# Pi3_Power_hat_Rev1.net
KiCad netlist of a schematic drawn in EAGLE
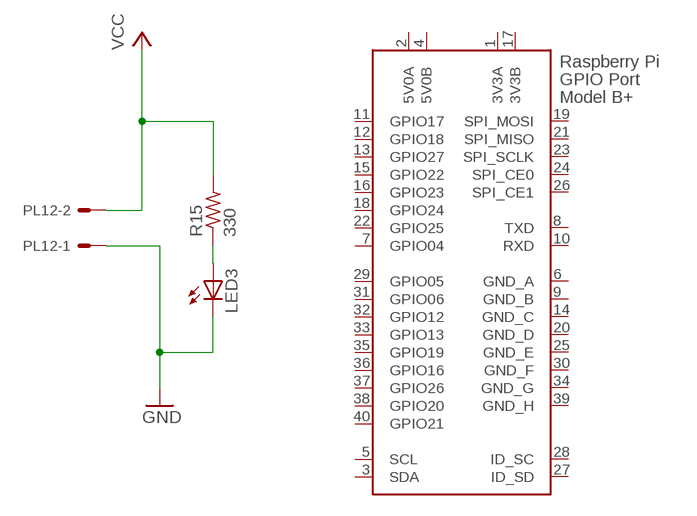
[diagram p0: schematic, sheet 1]
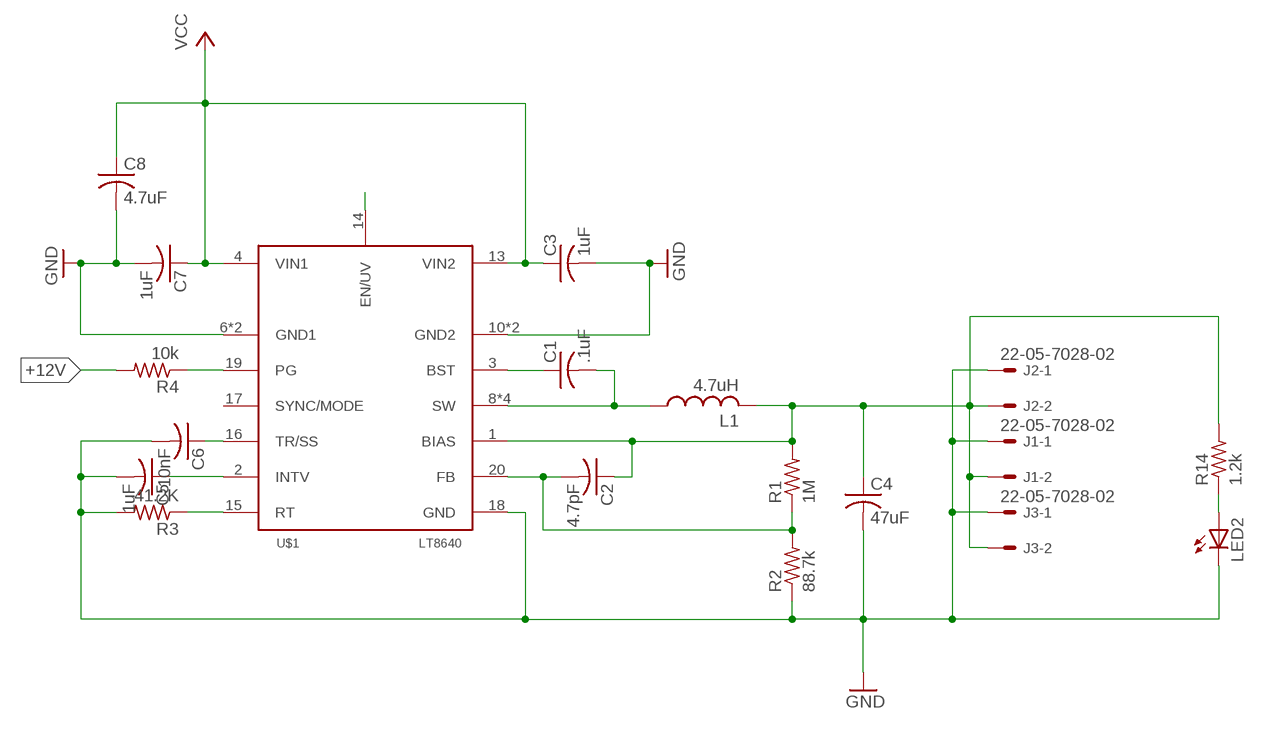
[diagram p1: schematic, sheet 2]
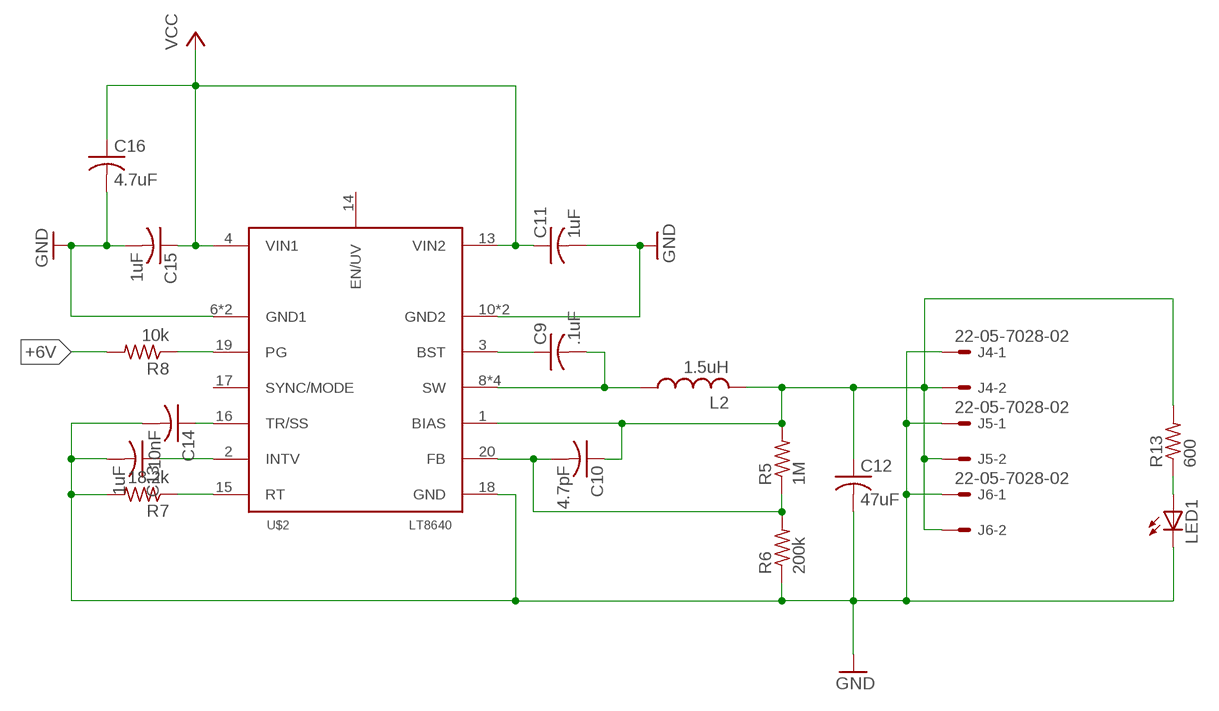
[diagram p2: schematic, sheet 3]
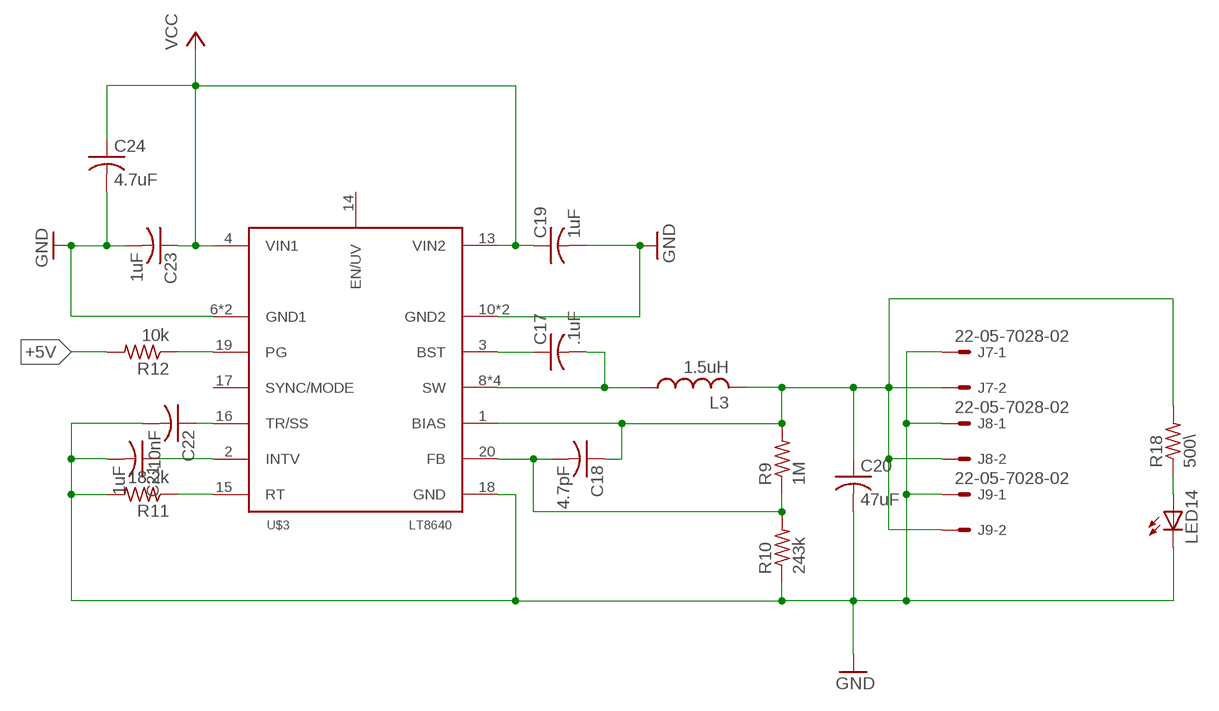
[diagram p3: schematic, sheet 4]

(export (version "E")
  (design (tool "Eeschema 10.0.6"))
  (components
    (comp (ref "LED3")
      (value "LEDCHIP-LED0603")
      (footprint "eagle-import:CHIP-LED0603")
      (libsource (lib "eagle-import") (part "LEDCHIP-LED0603"))
    )
    (comp (ref "PL12")
      (value "555X-2H")
      (footprint "eagle-import:5569-2")
      (libsource (lib "eagle-import") (part "555X-2H"))
    )
    (comp (ref "R15")
      (value "330")
      (footprint "eagle-import:R0402")
      (libsource (lib "eagle-import") (part "R-US_R0402"))
    )
    (comp (ref "X1")
      (value "RASPI_BOARD_B+#_E4P")
      (footprint "eagle-import:RASPI_BOARD_B+_EDGES_4DRILL_PAD")
      (libsource (lib "eagle-import") (part "RASPI_BOARD_B+#_E4P"))
    )
    (comp (ref "C1")
      (value ".1uF")
      (footprint "eagle-import:C0402")
      (libsource (lib "eagle-import") (part "C-USC0402"))
    )
    (comp (ref "C2")
      (value "4.7pF")
      (footprint "eagle-import:C0402")
      (libsource (lib "eagle-import") (part "C-USC0402"))
    )
    (comp (ref "C3")
      (value "1uF")
      (footprint "eagle-import:C0402")
      (libsource (lib "eagle-import") (part "C-USC0402"))
    )
    (comp (ref "C4")
      (value "47uF")
      (footprint "eagle-import:C1210")
      (libsource (lib "eagle-import") (part "C-USC1210"))
    )
    (comp (ref "C5")
      (value "1uF")
      (footprint "eagle-import:C0402")
      (libsource (lib "eagle-import") (part "C-USC0402"))
    )
    (comp (ref "C6")
      (value "10nF")
      (footprint "eagle-import:C0402")
      (libsource (lib "eagle-import") (part "C-USC0402"))
    )
    (comp (ref "C7")
      (value "1uF")
      (footprint "eagle-import:C0402")
      (libsource (lib "eagle-import") (part "C-USC0402"))
    )
    (comp (ref "C8")
      (value "4.7uF")
      (footprint "eagle-import:C0603")
      (libsource (lib "eagle-import") (part "C-USC0603"))
    )
    (comp (ref "J1")
      (value "22-05-7028-02")
      (footprint "eagle-import:7395-02")
      (libsource (lib "eagle-import") (part "22-?-0205-7028"))
    )
    (comp (ref "J2")
      (value "22-05-7028-02")
      (footprint "eagle-import:7395-02")
      (libsource (lib "eagle-import") (part "22-?-0205-7028"))
    )
    (comp (ref "J3")
      (value "22-05-7028-02")
      (footprint "eagle-import:7395-02")
      (libsource (lib "eagle-import") (part "22-?-0205-7028"))
    )
    (comp (ref "L1")
      (value "4.7uH")
      (footprint "eagle-import:IHLP2525EZER4R7M01-FOOT")
      (libsource (lib "eagle-import") (part "L-USIHLP2525EZER4R7M01"))
    )
    (comp (ref "LED2")
      (value "LEDCHIP-LED0603")
      (footprint "eagle-import:CHIP-LED0603")
      (libsource (lib "eagle-import") (part "LEDCHIP-LED0603"))
    )
    (comp (ref "R1")
      (value "1M")
      (footprint "eagle-import:R0402")
      (libsource (lib "eagle-import") (part "R-US_R0402"))
    )
    (comp (ref "R2")
      (value "88.7k")
      (footprint "eagle-import:R0402")
      (libsource (lib "eagle-import") (part "R-US_R0402"))
    )
    (comp (ref "R3")
      (value "41.2K")
      (footprint "eagle-import:R0402")
      (libsource (lib "eagle-import") (part "R-US_R0402"))
    )
    (comp (ref "R4")
      (value "10k")
      (footprint "eagle-import:R0402")
      (libsource (lib "eagle-import") (part "R-US_R0402"))
    )
    (comp (ref "R14")
      (value "1.2k")
      (footprint "eagle-import:R0402")
      (libsource (lib "eagle-import") (part "R-US_R0402"))
    )
    (comp (ref "U$1")
      (value "LT8640")
      (footprint "eagle-import:LT8640_FOOT")
      (libsource (lib "eagle-import") (part "LT8640"))
    )
    (comp (ref "C9")
      (value ".1uF")
      (footprint "eagle-import:C0402")
      (libsource (lib "eagle-import") (part "C-USC0402"))
    )
    (comp (ref "C10")
      (value "4.7pF")
      (footprint "eagle-import:C0402")
      (libsource (lib "eagle-import") (part "C-USC0402"))
    )
    (comp (ref "C11")
      (value "1uF")
      (footprint "eagle-import:C0402")
      (libsource (lib "eagle-import") (part "C-USC0402"))
    )
    (comp (ref "C12")
      (value "47uF")
      (footprint "eagle-import:C1210")
      (libsource (lib "eagle-import") (part "C-USC1210"))
    )
    (comp (ref "C13")
      (value "1uF")
      (footprint "eagle-import:C0402")
      (libsource (lib "eagle-import") (part "C-USC0402"))
    )
    (comp (ref "C14")
      (value "10nF")
      (footprint "eagle-import:C0402")
      (libsource (lib "eagle-import") (part "C-USC0402"))
    )
    (comp (ref "C15")
      (value "1uF")
      (footprint "eagle-import:C0402")
      (libsource (lib "eagle-import") (part "C-USC0402"))
    )
    (comp (ref "C16")
      (value "4.7uF")
      (footprint "eagle-import:C0603")
      (libsource (lib "eagle-import") (part "C-USC0603"))
    )
    (comp (ref "J4")
      (value "22-05-7028-02")
      (footprint "eagle-import:7395-02")
      (libsource (lib "eagle-import") (part "22-?-0205-7028"))
    )
    (comp (ref "J5")
      (value "22-05-7028-02")
      (footprint "eagle-import:7395-02")
      (libsource (lib "eagle-import") (part "22-?-0205-7028"))
    )
    (comp (ref "J6")
      (value "22-05-7028-02")
      (footprint "eagle-import:7395-02")
      (libsource (lib "eagle-import") (part "22-?-0205-7028"))
    )
    (comp (ref "L2")
      (value "1.5uH")
      (footprint "eagle-import:IHLP2525EZER4R7M01-FOOT")
      (libsource (lib "eagle-import") (part "L-USIHLP2525EZER4R7M01"))
    )
    (comp (ref "LED1")
      (value "LEDCHIP-LED0603")
      (footprint "eagle-import:CHIP-LED0603")
      (libsource (lib "eagle-import") (part "LEDCHIP-LED0603"))
    )
    (comp (ref "R5")
      (value "1M")
      (footprint "eagle-import:R0402")
      (libsource (lib "eagle-import") (part "R-US_R0402"))
    )
    (comp (ref "R6")
      (value "200k")
      (footprint "eagle-import:R0402")
      (libsource (lib "eagle-import") (part "R-US_R0402"))
    )
    (comp (ref "R7")
      (value "18.2k")
      (footprint "eagle-import:R0402")
      (libsource (lib "eagle-import") (part "R-US_R0402"))
    )
    (comp (ref "R8")
      (value "10k")
      (footprint "eagle-import:R0402")
      (libsource (lib "eagle-import") (part "R-US_R0402"))
    )
    (comp (ref "R13")
      (value "600")
      (footprint "eagle-import:R0402")
      (libsource (lib "eagle-import") (part "R-US_R0402"))
    )
    (comp (ref "U$2")
      (value "LT8640")
      (footprint "eagle-import:LT8640_FOOT")
      (libsource (lib "eagle-import") (part "LT8640"))
    )
    (comp (ref "C17")
      (value ".1uF")
      (footprint "eagle-import:C0402")
      (libsource (lib "eagle-import") (part "C-USC0402"))
    )
    (comp (ref "C18")
      (value "4.7pF")
      (footprint "eagle-import:C0402")
      (libsource (lib "eagle-import") (part "C-USC0402"))
    )
    (comp (ref "C19")
      (value "1uF")
      (footprint "eagle-import:C0402")
      (libsource (lib "eagle-import") (part "C-USC0402"))
    )
    (comp (ref "C20")
      (value "47uF")
      (footprint "eagle-import:C1210")
      (libsource (lib "eagle-import") (part "C-USC1210"))
    )
    (comp (ref "C21")
      (value "1uF")
      (footprint "eagle-import:C0402")
      (libsource (lib "eagle-import") (part "C-USC0402"))
    )
    (comp (ref "C22")
      (value "10nF")
      (footprint "eagle-import:C0402")
      (libsource (lib "eagle-import") (part "C-USC0402"))
    )
    (comp (ref "C23")
      (value "1uF")
      (footprint "eagle-import:C0402")
      (libsource (lib "eagle-import") (part "C-USC0402"))
    )
    (comp (ref "C24")
      (value "4.7uF")
      (footprint "eagle-import:C0603")
      (libsource (lib "eagle-import") (part "C-USC0603"))
    )
    (comp (ref "J7")
      (value "22-05-7028-02")
      (footprint "eagle-import:7395-02")
      (libsource (lib "eagle-import") (part "22-?-0205-7028"))
    )
    (comp (ref "J8")
      (value "22-05-7028-02")
      (footprint "eagle-import:7395-02")
      (libsource (lib "eagle-import") (part "22-?-0205-7028"))
    )
    (comp (ref "J9")
      (value "22-05-7028-02")
      (footprint "eagle-import:7395-02")
      (libsource (lib "eagle-import") (part "22-?-0205-7028"))
    )
    (comp (ref "L3")
      (value "1.5uH")
      (footprint "eagle-import:IHLP2525EZER4R7M01-FOOT")
      (libsource (lib "eagle-import") (part "L-USIHLP2525EZER4R7M01"))
    )
    (comp (ref "LED14")
      (value "LEDCHIP-LED0603")
      (footprint "eagle-import:CHIP-LED0603")
      (libsource (lib "eagle-import") (part "LEDCHIP-LED0603"))
    )
    (comp (ref "R9")
      (value "1M")
      (footprint "eagle-import:R0402")
      (libsource (lib "eagle-import") (part "R-US_R0402"))
    )
    (comp (ref "R10")
      (value "243k")
      (footprint "eagle-import:R0402")
      (libsource (lib "eagle-import") (part "R-US_R0402"))
    )
    (comp (ref "R11")
      (value "18.2k")
      (footprint "eagle-import:R0402")
      (libsource (lib "eagle-import") (part "R-US_R0402"))
    )
    (comp (ref "R12")
      (value "10k")
      (footprint "eagle-import:R0402")
      (libsource (lib "eagle-import") (part "R-US_R0402"))
    )
    (comp (ref "R18")
      (value "500\\")
      (footprint "eagle-import:R0402")
      (libsource (lib "eagle-import") (part "R-US_R0402"))
    )
    (comp (ref "U$3")
      (value "LT8640")
      (footprint "eagle-import:LT8640_FOOT")
      (libsource (lib "eagle-import") (part "LT8640"))
    )
  )
  (nets
    (net (code "1") (name "+5V") (class "Default")
      (node (ref "C18") (pin "1") (pinfunction "1_1") (pintype "passive"))
      (node (ref "C20") (pin "1") (pinfunction "1_1") (pintype "passive"))
      (node (ref "J7") (pin "2") (pinfunction "S_2") (pintype "passive"))
      (node (ref "J8") (pin "2") (pinfunction "S_2") (pintype "passive"))
      (node (ref "J9") (pin "2") (pinfunction "S_2") (pintype "passive"))
      (node (ref "L3") (pin "2") (pinfunction "2_2") (pintype "passive"))
      (node (ref "R12") (pin "2") (pinfunction "2_2") (pintype "passive"))
      (node (ref "R18") (pin "2") (pinfunction "2_2") (pintype "passive"))
      (node (ref "R9") (pin "2") (pinfunction "2_2") (pintype "passive"))
      (node (ref "U$3") (pin "1") (pinfunction "BIAS_1") (pintype "bidirectional"))
    )
    (net (code "2") (name "+6V") (class "Default")
      (node (ref "C10") (pin "1") (pinfunction "1_1") (pintype "passive"))
      (node (ref "C12") (pin "1") (pinfunction "1_1") (pintype "passive"))
      (node (ref "J4") (pin "2") (pinfunction "S_2") (pintype "passive"))
      (node (ref "J5") (pin "2") (pinfunction "S_2") (pintype "passive"))
      (node (ref "J6") (pin "2") (pinfunction "S_2") (pintype "passive"))
      (node (ref "L2") (pin "2") (pinfunction "2_2") (pintype "passive"))
      (node (ref "R13") (pin "2") (pinfunction "2_2") (pintype "passive"))
      (node (ref "R5") (pin "2") (pinfunction "2_2") (pintype "passive"))
      (node (ref "R8") (pin "2") (pinfunction "2_2") (pintype "passive"))
      (node (ref "U$2") (pin "1") (pinfunction "BIAS_1") (pintype "bidirectional"))
    )
    (net (code "3") (name "+12V") (class "Default")
      (node (ref "C2") (pin "1") (pinfunction "1_1") (pintype "passive"))
      (node (ref "C4") (pin "1") (pinfunction "1_1") (pintype "passive"))
      (node (ref "J1") (pin "2") (pinfunction "S_2") (pintype "passive"))
      (node (ref "J2") (pin "2") (pinfunction "S_2") (pintype "passive"))
      (node (ref "J3") (pin "2") (pinfunction "S_2") (pintype "passive"))
      (node (ref "L1") (pin "2") (pinfunction "2_2") (pintype "passive"))
      (node (ref "R1") (pin "2") (pinfunction "2_2") (pintype "passive"))
      (node (ref "R14") (pin "2") (pinfunction "2_2") (pintype "passive"))
      (node (ref "R4") (pin "2") (pinfunction "2_2") (pintype "passive"))
      (node (ref "U$1") (pin "1") (pinfunction "BIAS_1") (pintype "bidirectional"))
    )
    (net (code "4") (name "3V3A") (class "Default")
      (node (ref "X1") (pin "1") (pinfunction "3V3A_1") (pintype "power_in"))
    )
    (net (code "5") (name "3V3B") (class "Default")
      (node (ref "X1") (pin "17") (pinfunction "3V3B_17") (pintype "power_in"))
    )
    (net (code "6") (name "5V0A") (class "Default")
      (node (ref "X1") (pin "2") (pinfunction "5V0A_2") (pintype "power_in"))
    )
    (net (code "7") (name "5V0B") (class "Default")
      (node (ref "X1") (pin "4") (pinfunction "5V0B_4") (pintype "power_in"))
    )
    (net (code "8") (name "GND") (class "Default")
      (node (ref "C11") (pin "2") (pinfunction "2_2") (pintype "passive"))
      (node (ref "C12") (pin "2") (pinfunction "2_2") (pintype "passive"))
      (node (ref "C13") (pin "2") (pinfunction "2_2") (pintype "passive"))
      (node (ref "C14") (pin "2") (pinfunction "2_2") (pintype "passive"))
      (node (ref "C15") (pin "2") (pinfunction "2_2") (pintype "passive"))
      (node (ref "C16") (pin "2") (pinfunction "2_2") (pintype "passive"))
      (node (ref "C19") (pin "2") (pinfunction "2_2") (pintype "passive"))
      (node (ref "C20") (pin "2") (pinfunction "2_2") (pintype "passive"))
      (node (ref "C21") (pin "2") (pinfunction "2_2") (pintype "passive"))
      (node (ref "C22") (pin "2") (pinfunction "2_2") (pintype "passive"))
      (node (ref "C23") (pin "2") (pinfunction "2_2") (pintype "passive"))
      (node (ref "C24") (pin "2") (pinfunction "2_2") (pintype "passive"))
      (node (ref "C3") (pin "2") (pinfunction "2_2") (pintype "passive"))
      (node (ref "C4") (pin "2") (pinfunction "2_2") (pintype "passive"))
      (node (ref "C5") (pin "2") (pinfunction "2_2") (pintype "passive"))
      (node (ref "C6") (pin "2") (pinfunction "2_2") (pintype "passive"))
      (node (ref "C7") (pin "2") (pinfunction "2_2") (pintype "passive"))
      (node (ref "C8") (pin "2") (pinfunction "2_2") (pintype "passive"))
      (node (ref "J1") (pin "1") (pinfunction "S_1") (pintype "passive"))
      (node (ref "J2") (pin "1") (pinfunction "S_1") (pintype "passive"))
      (node (ref "J3") (pin "1") (pinfunction "S_1") (pintype "passive"))
      (node (ref "J4") (pin "1") (pinfunction "S_1") (pintype "passive"))
      (node (ref "J5") (pin "1") (pinfunction "S_1") (pintype "passive"))
      (node (ref "J6") (pin "1") (pinfunction "S_1") (pintype "passive"))
      (node (ref "J7") (pin "1") (pinfunction "S_1") (pintype "passive"))
      (node (ref "J8") (pin "1") (pinfunction "S_1") (pintype "passive"))
      (node (ref "J9") (pin "1") (pinfunction "S_1") (pintype "passive"))
      (node (ref "LED1") (pin "C") (pinfunction "C_C") (pintype "passive"))
      (node (ref "LED14") (pin "C") (pinfunction "C_C") (pintype "passive"))
      (node (ref "LED2") (pin "C") (pinfunction "C_C") (pintype "passive"))
      (node (ref "LED3") (pin "C") (pinfunction "C_C") (pintype "passive"))
      (node (ref "PL12") (pin "1") (pinfunction "S_1") (pintype "passive"))
      (node (ref "R10") (pin "1") (pinfunction "1_1") (pintype "passive"))
      (node (ref "R11") (pin "2") (pinfunction "2_2") (pintype "passive"))
      (node (ref "R2") (pin "1") (pinfunction "1_1") (pintype "passive"))
      (node (ref "R3") (pin "2") (pinfunction "2_2") (pintype "passive"))
      (node (ref "R6") (pin "1") (pinfunction "1_1") (pintype "passive"))
      (node (ref "R7") (pin "2") (pinfunction "2_2") (pintype "passive"))
      (node (ref "U$1") (pin "10") (pinfunction "GND2_10") (pintype "bidirectional"))
      (node (ref "U$1") (pin "11") (pinfunction "GND2_11") (pintype "bidirectional"))
      (node (ref "U$1") (pin "18") (pinfunction "GND_18") (pintype "bidirectional"))
      (node (ref "U$1") (pin "6") (pinfunction "GND1_6") (pintype "bidirectional"))
      (node (ref "U$1") (pin "7") (pinfunction "GND1_7") (pintype "bidirectional"))
      (node (ref "U$2") (pin "10") (pinfunction "GND2_10") (pintype "bidirectional"))
      (node (ref "U$2") (pin "11") (pinfunction "GND2_11") (pintype "bidirectional"))
      (node (ref "U$2") (pin "18") (pinfunction "GND_18") (pintype "bidirectional"))
      (node (ref "U$2") (pin "6") (pinfunction "GND1_6") (pintype "bidirectional"))
      (node (ref "U$2") (pin "7") (pinfunction "GND1_7") (pintype "bidirectional"))
      (node (ref "U$3") (pin "10") (pinfunction "GND2_10") (pintype "bidirectional"))
      (node (ref "U$3") (pin "11") (pinfunction "GND2_11") (pintype "bidirectional"))
      (node (ref "U$3") (pin "18") (pinfunction "GND_18") (pintype "bidirectional"))
      (node (ref "U$3") (pin "6") (pinfunction "GND1_6") (pintype "bidirectional"))
      (node (ref "U$3") (pin "7") (pinfunction "GND1_7") (pintype "bidirectional"))
    )
    (net (code "9") (name "GND_A") (class "Default")
      (node (ref "X1") (pin "6") (pinfunction "GND_A_6") (pintype "power_in"))
    )
    (net (code "10") (name "GND_B") (class "Default")
      (node (ref "X1") (pin "9") (pinfunction "GND_B_9") (pintype "power_in"))
    )
    (net (code "11") (name "GND_C") (class "Default")
      (node (ref "X1") (pin "14") (pinfunction "GND_C_14") (pintype "power_in"))
    )
    (net (code "12") (name "GND_D") (class "Default")
      (node (ref "X1") (pin "20") (pinfunction "GND_D_20") (pintype "power_in"))
    )
    (net (code "13") (name "GND_E") (class "Default")
      (node (ref "X1") (pin "25") (pinfunction "GND_E_25") (pintype "power_in"))
    )
    (net (code "14") (name "GND_F") (class "Default")
      (node (ref "X1") (pin "30") (pinfunction "GND_F_30") (pintype "power_in"))
    )
    (net (code "15") (name "GND_G") (class "Default")
      (node (ref "X1") (pin "34") (pinfunction "GND_G_34") (pintype "power_in"))
    )
    (net (code "16") (name "GND_H") (class "Default")
      (node (ref "X1") (pin "39") (pinfunction "GND_H_39") (pintype "power_in"))
    )
    (net (code "17") (name "Net-(C1-Pad2)") (class "Default")
      (node (ref "C1") (pin "2") (pinfunction "2_2") (pintype "passive"))
      (node (ref "L1") (pin "1") (pinfunction "1_1") (pintype "passive"))
      (node (ref "U$1") (pin "21") (pinfunction "SW_21") (pintype "bidirectional"))
      (node (ref "U$1") (pin "22") (pinfunction "SW_22") (pintype "bidirectional"))
      (node (ref "U$1") (pin "8") (pinfunction "SW_8") (pintype "bidirectional"))
      (node (ref "U$1") (pin "9") (pinfunction "SW_9") (pintype "bidirectional"))
    )
    (net (code "18") (name "Net-(C9-Pad2)") (class "Default")
      (node (ref "C9") (pin "2") (pinfunction "2_2") (pintype "passive"))
      (node (ref "L2") (pin "1") (pinfunction "1_1") (pintype "passive"))
      (node (ref "U$2") (pin "21") (pinfunction "SW_21") (pintype "bidirectional"))
      (node (ref "U$2") (pin "22") (pinfunction "SW_22") (pintype "bidirectional"))
      (node (ref "U$2") (pin "8") (pinfunction "SW_8") (pintype "bidirectional"))
      (node (ref "U$2") (pin "9") (pinfunction "SW_9") (pintype "bidirectional"))
    )
    (net (code "19") (name "Net-(C17-Pad2)") (class "Default")
      (node (ref "C17") (pin "2") (pinfunction "2_2") (pintype "passive"))
      (node (ref "L3") (pin "1") (pinfunction "1_1") (pintype "passive"))
      (node (ref "U$3") (pin "21") (pinfunction "SW_21") (pintype "bidirectional"))
      (node (ref "U$3") (pin "22") (pinfunction "SW_22") (pintype "bidirectional"))
      (node (ref "U$3") (pin "8") (pinfunction "SW_8") (pintype "bidirectional"))
      (node (ref "U$3") (pin "9") (pinfunction "SW_9") (pintype "bidirectional"))
    )
    (net (code "20") (name "Net-(LED1-PadA)") (class "Default")
      (node (ref "LED1") (pin "A") (pinfunction "A_A") (pintype "passive"))
      (node (ref "R13") (pin "1") (pinfunction "1_1") (pintype "passive"))
    )
    (net (code "21") (name "Net-(LED2-PadA)") (class "Default")
      (node (ref "LED2") (pin "A") (pinfunction "A_A") (pintype "passive"))
      (node (ref "R14") (pin "1") (pinfunction "1_1") (pintype "passive"))
    )
    (net (code "22") (name "Net-(LED3-PadA)") (class "Default")
      (node (ref "LED3") (pin "A") (pinfunction "A_A") (pintype "passive"))
      (node (ref "R15") (pin "1") (pinfunction "1_1") (pintype "passive"))
    )
    (net (code "23") (name "Net-(LED14-PadA)") (class "Default")
      (node (ref "LED14") (pin "A") (pinfunction "A_A") (pintype "passive"))
      (node (ref "R18") (pin "1") (pinfunction "1_1") (pintype "passive"))
    )
    (net (code "24") (name "Net-(U$1-BST)") (class "Default")
      (node (ref "C1") (pin "1") (pinfunction "1_1") (pintype "passive"))
      (node (ref "U$1") (pin "3") (pinfunction "BST_3") (pintype "bidirectional"))
    )
    (net (code "25") (name "Net-(U$1-FB)") (class "Default")
      (node (ref "C2") (pin "2") (pinfunction "2_2") (pintype "passive"))
      (node (ref "R1") (pin "1") (pinfunction "1_1") (pintype "passive"))
      (node (ref "R2") (pin "2") (pinfunction "2_2") (pintype "passive"))
      (node (ref "U$1") (pin "20") (pinfunction "FB_20") (pintype "bidirectional"))
    )
    (net (code "26") (name "Net-(U$1-INTV)") (class "Default")
      (node (ref "C5") (pin "1") (pinfunction "1_1") (pintype "passive"))
      (node (ref "U$1") (pin "2") (pinfunction "INTV_2") (pintype "bidirectional"))
    )
    (net (code "27") (name "Net-(U$1-PG)") (class "Default")
      (node (ref "R4") (pin "1") (pinfunction "1_1") (pintype "passive"))
      (node (ref "U$1") (pin "19") (pinfunction "PG_19") (pintype "bidirectional"))
    )
    (net (code "28") (name "Net-(U$1-RT)") (class "Default")
      (node (ref "R3") (pin "1") (pinfunction "1_1") (pintype "passive"))
      (node (ref "U$1") (pin "15") (pinfunction "RT_15") (pintype "bidirectional"))
    )
    (net (code "29") (name "Net-(U$1-TR{slash}SS)") (class "Default")
      (node (ref "C6") (pin "1") (pinfunction "1_1") (pintype "passive"))
      (node (ref "U$1") (pin "16") (pinfunction "TR/SS_16") (pintype "bidirectional"))
    )
    (net (code "30") (name "Net-(U$2-BST)") (class "Default")
      (node (ref "C9") (pin "1") (pinfunction "1_1") (pintype "passive"))
      (node (ref "U$2") (pin "3") (pinfunction "BST_3") (pintype "bidirectional"))
    )
    (net (code "31") (name "Net-(U$2-FB)") (class "Default")
      (node (ref "C10") (pin "2") (pinfunction "2_2") (pintype "passive"))
      (node (ref "R5") (pin "1") (pinfunction "1_1") (pintype "passive"))
      (node (ref "R6") (pin "2") (pinfunction "2_2") (pintype "passive"))
      (node (ref "U$2") (pin "20") (pinfunction "FB_20") (pintype "bidirectional"))
    )
    (net (code "32") (name "Net-(U$2-INTV)") (class "Default")
      (node (ref "C13") (pin "1") (pinfunction "1_1") (pintype "passive"))
      (node (ref "U$2") (pin "2") (pinfunction "INTV_2") (pintype "bidirectional"))
    )
    (net (code "33") (name "Net-(U$2-PG)") (class "Default")
      (node (ref "R8") (pin "1") (pinfunction "1_1") (pintype "passive"))
      (node (ref "U$2") (pin "19") (pinfunction "PG_19") (pintype "bidirectional"))
    )
    (net (code "34") (name "Net-(U$2-RT)") (class "Default")
      (node (ref "R7") (pin "1") (pinfunction "1_1") (pintype "passive"))
      (node (ref "U$2") (pin "15") (pinfunction "RT_15") (pintype "bidirectional"))
    )
    (net (code "35") (name "Net-(U$2-TR{slash}SS)") (class "Default")
      (node (ref "C14") (pin "1") (pinfunction "1_1") (pintype "passive"))
      (node (ref "U$2") (pin "16") (pinfunction "TR/SS_16") (pintype "bidirectional"))
    )
    (net (code "36") (name "Net-(U$3-BST)") (class "Default")
      (node (ref "C17") (pin "1") (pinfunction "1_1") (pintype "passive"))
      (node (ref "U$3") (pin "3") (pinfunction "BST_3") (pintype "bidirectional"))
    )
    (net (code "37") (name "Net-(U$3-FB)") (class "Default")
      (node (ref "C18") (pin "2") (pinfunction "2_2") (pintype "passive"))
      (node (ref "R10") (pin "2") (pinfunction "2_2") (pintype "passive"))
      (node (ref "R9") (pin "1") (pinfunction "1_1") (pintype "passive"))
      (node (ref "U$3") (pin "20") (pinfunction "FB_20") (pintype "bidirectional"))
    )
    (net (code "38") (name "Net-(U$3-INTV)") (class "Default")
      (node (ref "C21") (pin "1") (pinfunction "1_1") (pintype "passive"))
      (node (ref "U$3") (pin "2") (pinfunction "INTV_2") (pintype "bidirectional"))
    )
    (net (code "39") (name "Net-(U$3-PG)") (class "Default")
      (node (ref "R12") (pin "1") (pinfunction "1_1") (pintype "passive"))
      (node (ref "U$3") (pin "19") (pinfunction "PG_19") (pintype "bidirectional"))
    )
    (net (code "40") (name "Net-(U$3-RT)") (class "Default")
      (node (ref "R11") (pin "1") (pinfunction "1_1") (pintype "passive"))
      (node (ref "U$3") (pin "15") (pinfunction "RT_15") (pintype "bidirectional"))
    )
    (net (code "41") (name "Net-(U$3-TR{slash}SS)") (class "Default")
      (node (ref "C22") (pin "1") (pinfunction "1_1") (pintype "passive"))
      (node (ref "U$3") (pin "16") (pinfunction "TR/SS_16") (pintype "bidirectional"))
    )
    (net (code "42") (name "VCC") (class "Default")
      (node (ref "C11") (pin "1") (pinfunction "1_1") (pintype "passive"))
      (node (ref "C15") (pin "1") (pinfunction "1_1") (pintype "passive"))
      (node (ref "C16") (pin "1") (pinfunction "1_1") (pintype "passive"))
      (node (ref "C19") (pin "1") (pinfunction "1_1") (pintype "passive"))
      (node (ref "C23") (pin "1") (pinfunction "1_1") (pintype "passive"))
      (node (ref "C24") (pin "1") (pinfunction "1_1") (pintype "passive"))
      (node (ref "C3") (pin "1") (pinfunction "1_1") (pintype "passive"))
      (node (ref "C7") (pin "1") (pinfunction "1_1") (pintype "passive"))
      (node (ref "C8") (pin "1") (pinfunction "1_1") (pintype "passive"))
      (node (ref "PL12") (pin "2") (pinfunction "S_2") (pintype "passive"))
      (node (ref "R15") (pin "2") (pinfunction "2_2") (pintype "passive"))
      (node (ref "U$1") (pin "13") (pinfunction "VIN2_13") (pintype "bidirectional"))
      (node (ref "U$1") (pin "4") (pinfunction "VIN1_4") (pintype "bidirectional"))
      (node (ref "U$2") (pin "13") (pinfunction "VIN2_13") (pintype "bidirectional"))
      (node (ref "U$2") (pin "4") (pinfunction "VIN1_4") (pintype "bidirectional"))
      (node (ref "U$3") (pin "13") (pinfunction "VIN2_13") (pintype "bidirectional"))
      (node (ref "U$3") (pin "4") (pinfunction "VIN1_4") (pintype "bidirectional"))
    )
    (net (code "43") (name "unconnected-(U$1-EN{slash}UV-Pad14)") (class "Default")
      (node (ref "U$1") (pin "14") (pinfunction "EN/UV_14") (pintype "bidirectional"))
    )
    (net (code "44") (name "unconnected-(U$1-SYNC{slash}MODE-Pad17)") (class "Default")
      (node (ref "U$1") (pin "17") (pinfunction "SYNC/MODE_17") (pintype "bidirectional"))
    )
    (net (code "45") (name "unconnected-(U$2-EN{slash}UV-Pad14)") (class "Default")
      (node (ref "U$2") (pin "14") (pinfunction "EN/UV_14") (pintype "bidirectional"))
    )
    (net (code "46") (name "unconnected-(U$2-SYNC{slash}MODE-Pad17)") (class "Default")
      (node (ref "U$2") (pin "17") (pinfunction "SYNC/MODE_17") (pintype "bidirectional"))
    )
    (net (code "47") (name "unconnected-(U$3-EN{slash}UV-Pad14)") (class "Default")
      (node (ref "U$3") (pin "14") (pinfunction "EN/UV_14") (pintype "bidirectional"))
    )
    (net (code "48") (name "unconnected-(U$3-SYNC{slash}MODE-Pad17)") (class "Default")
      (node (ref "U$3") (pin "17") (pinfunction "SYNC/MODE_17") (pintype "bidirectional"))
    )
    (net (code "49") (name "unconnected-(X1-GPIO04-Pad7)") (class "Default")
      (node (ref "X1") (pin "7") (pinfunction "GPIO04_7") (pintype "bidirectional"))
    )
    (net (code "50") (name "unconnected-(X1-GPIO05-Pad29)") (class "Default")
      (node (ref "X1") (pin "29") (pinfunction "GPIO05_29") (pintype "no_connect"))
    )
    (net (code "51") (name "unconnected-(X1-GPIO06-Pad31)") (class "Default")
      (node (ref "X1") (pin "31") (pinfunction "GPIO06_31") (pintype "no_connect"))
    )
    (net (code "52") (name "unconnected-(X1-GPIO12-Pad32)") (class "Default")
      (node (ref "X1") (pin "32") (pinfunction "GPIO12_32") (pintype "no_connect"))
    )
    (net (code "53") (name "unconnected-(X1-GPIO13-Pad33)") (class "Default")
      (node (ref "X1") (pin "33") (pinfunction "GPIO13_33") (pintype "no_connect"))
    )
    (net (code "54") (name "unconnected-(X1-GPIO16-Pad36)") (class "Default")
      (node (ref "X1") (pin "36") (pinfunction "GPIO16_36") (pintype "no_connect"))
    )
    (net (code "55") (name "unconnected-(X1-GPIO17-Pad11)") (class "Default")
      (node (ref "X1") (pin "11") (pinfunction "GPIO17_11") (pintype "bidirectional"))
    )
    (net (code "56") (name "unconnected-(X1-GPIO18-Pad12)") (class "Default")
      (node (ref "X1") (pin "12") (pinfunction "GPIO18_12") (pintype "bidirectional"))
    )
    (net (code "57") (name "unconnected-(X1-GPIO19-Pad35)") (class "Default")
      (node (ref "X1") (pin "35") (pinfunction "GPIO19_35") (pintype "no_connect"))
    )
    (net (code "58") (name "unconnected-(X1-GPIO20-Pad38)") (class "Default")
      (node (ref "X1") (pin "38") (pinfunction "GPIO20_38") (pintype "no_connect"))
    )
    (net (code "59") (name "unconnected-(X1-GPIO21-Pad40)") (class "Default")
      (node (ref "X1") (pin "40") (pinfunction "GPIO21_40") (pintype "no_connect"))
    )
    (net (code "60") (name "unconnected-(X1-GPIO22-Pad15)") (class "Default")
      (node (ref "X1") (pin "15") (pinfunction "GPIO22_15") (pintype "bidirectional"))
    )
    (net (code "61") (name "unconnected-(X1-GPIO23-Pad16)") (class "Default")
      (node (ref "X1") (pin "16") (pinfunction "GPIO23_16") (pintype "bidirectional"))
    )
    (net (code "62") (name "unconnected-(X1-GPIO24-Pad18)") (class "Default")
      (node (ref "X1") (pin "18") (pinfunction "GPIO24_18") (pintype "bidirectional"))
    )
    (net (code "63") (name "unconnected-(X1-GPIO25-Pad22)") (class "Default")
      (node (ref "X1") (pin "22") (pinfunction "GPIO25_22") (pintype "bidirectional"))
    )
    (net (code "64") (name "unconnected-(X1-GPIO26-Pad37)") (class "Default")
      (node (ref "X1") (pin "37") (pinfunction "GPIO26_37") (pintype "no_connect"))
    )
    (net (code "65") (name "unconnected-(X1-GPIO27-Pad13)") (class "Default")
      (node (ref "X1") (pin "13") (pinfunction "GPIO27_13") (pintype "bidirectional"))
    )
    (net (code "66") (name "unconnected-(X1-ID_SC-Pad28)") (class "Default")
      (node (ref "X1") (pin "28") (pinfunction "ID_SC_28") (pintype "no_connect"))
    )
    (net (code "67") (name "unconnected-(X1-ID_SD-Pad27)") (class "Default")
      (node (ref "X1") (pin "27") (pinfunction "ID_SD_27") (pintype "no_connect"))
    )
    (net (code "68") (name "unconnected-(X1-RXD-Pad10)") (class "Default")
      (node (ref "X1") (pin "10") (pinfunction "RXD_10") (pintype "bidirectional"))
    )
    (net (code "69") (name "unconnected-(X1-SCL-Pad5)") (class "Default")
      (node (ref "X1") (pin "5") (pinfunction "SCL_5") (pintype "bidirectional"))
    )
    (net (code "70") (name "unconnected-(X1-SDA-Pad3)") (class "Default")
      (node (ref "X1") (pin "3") (pinfunction "SDA_3") (pintype "bidirectional"))
    )
    (net (code "71") (name "unconnected-(X1-SPI_CE0-Pad24)") (class "Default")
      (node (ref "X1") (pin "24") (pinfunction "SPI_CE0_24") (pintype "bidirectional"))
    )
    (net (code "72") (name "unconnected-(X1-SPI_CE1-Pad26)") (class "Default")
      (node (ref "X1") (pin "26") (pinfunction "SPI_CE1_26") (pintype "bidirectional"))
    )
    (net (code "73") (name "unconnected-(X1-SPI_MISO-Pad21)") (class "Default")
      (node (ref "X1") (pin "21") (pinfunction "SPI_MISO_21") (pintype "bidirectional"))
    )
    (net (code "74") (name "unconnected-(X1-SPI_MOSI-Pad19)") (class "Default")
      (node (ref "X1") (pin "19") (pinfunction "SPI_MOSI_19") (pintype "bidirectional"))
    )
    (net (code "75") (name "unconnected-(X1-SPI_SCLK-Pad23)") (class "Default")
      (node (ref "X1") (pin "23") (pinfunction "SPI_SCLK_23") (pintype "bidirectional"))
    )
    (net (code "76") (name "unconnected-(X1-TXD-Pad8)") (class "Default")
      (node (ref "X1") (pin "8") (pinfunction "TXD_8") (pintype "bidirectional"))
    )
  )
)
